# Adafruit_CH9328_UART_to_HID_Keyboard_Bre.net
KiCad netlist of a schematic drawn in EAGLE
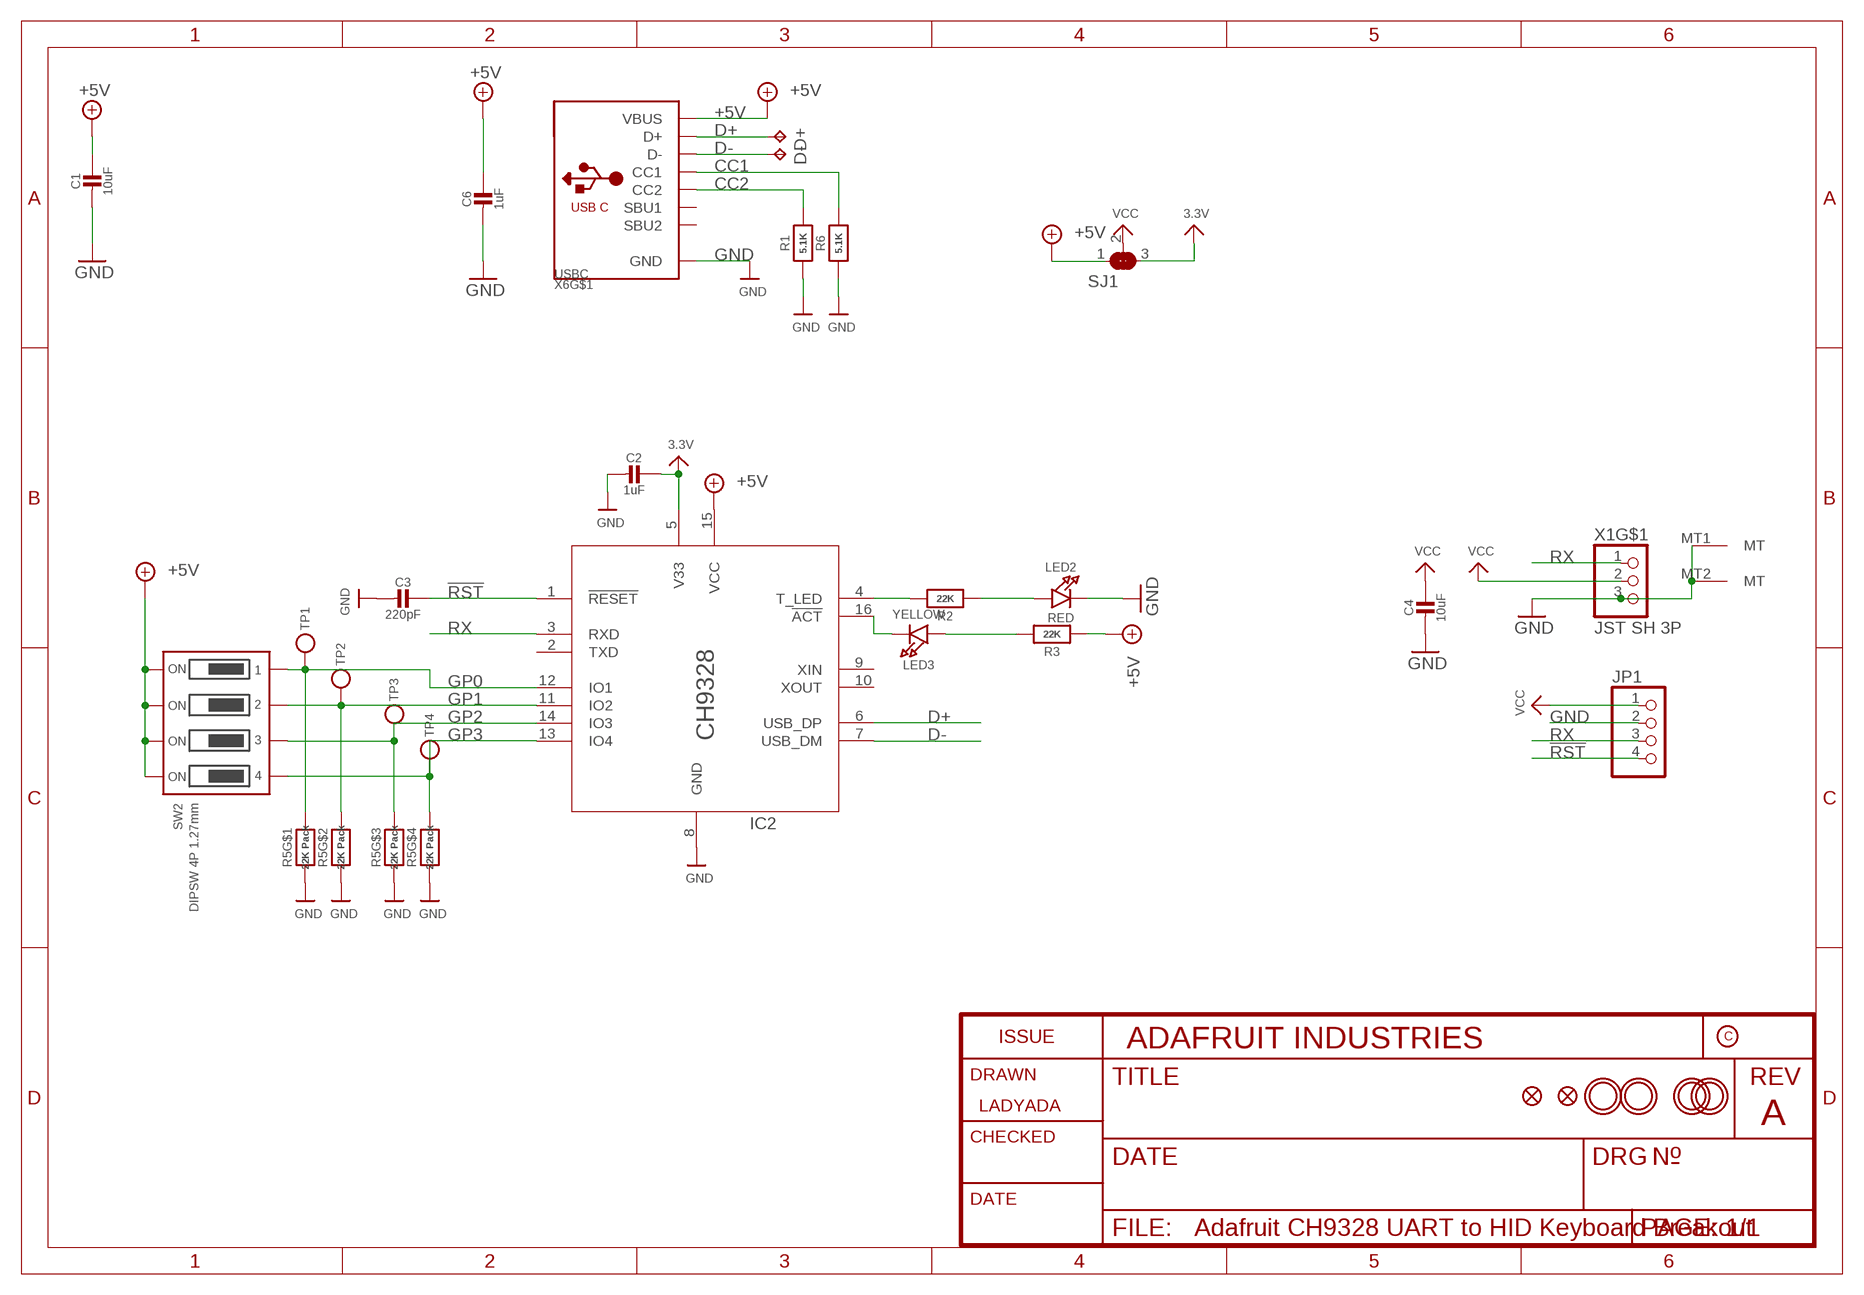
[diagram p0: schematic, sheet 1]

(export (version "E")
  (design (tool "Eeschema 10.0.6"))
  (components
    (comp (ref "C1")
      (value "10uF")
      (footprint "eagle-import:0805-NO")
      (libsource (lib "eagle-import") (part "CAP_CERAMIC0805-NOOUTLINE"))
    )
    (comp (ref "C2")
      (value "1uF")
      (footprint "eagle-import:0603-NO")
      (libsource (lib "eagle-import") (part "CAP_CERAMIC0603_NO"))
    )
    (comp (ref "C3")
      (value "220pF")
      (footprint "eagle-import:0603-NO")
      (libsource (lib "eagle-import") (part "CAP_CERAMIC0603_NO"))
    )
    (comp (ref "C4")
      (value "10uF")
      (footprint "eagle-import:0805-NO")
      (libsource (lib "eagle-import") (part "CAP_CERAMIC0805-NOOUTLINE"))
    )
    (comp (ref "C6")
      (value "1uF")
      (footprint "eagle-import:0603-NO")
      (libsource (lib "eagle-import") (part "CAP_CERAMIC0603_NO"))
    )
    (comp (ref "D+")
      (value "TPTP17R")
      (footprint "eagle-import:TP17R")
      (libsource (lib "eagle-import") (part "TPTP17R"))
    )
    (comp (ref "D-")
      (value "TPTP17R")
      (footprint "eagle-import:TP17R")
      (libsource (lib "eagle-import") (part "TPTP17R"))
    )
    (comp (ref "FID1")
      (value "FIDUCIAL_0.5MM")
      (footprint "eagle-import:FIDUCIAL_0.5MM")
      (libsource (lib "eagle-import") (part "FIDUCIAL_0.5MM"))
    )
    (comp (ref "FID2")
      (value "FIDUCIAL_0.5MM")
      (footprint "eagle-import:FIDUCIAL_0.5MM")
      (libsource (lib "eagle-import") (part "FIDUCIAL_0.5MM"))
    )
    (comp (ref "IC2")
      (value "CH9328_SKINNY")
      (footprint "eagle-import:SO16_SKINNY")
      (libsource (lib "eagle-import") (part "CH9328_SKINNY"))
    )
    (comp (ref "JP1")
      (value "HEADER-1X4ROUND")
      (footprint "eagle-import:1X04_ROUND")
      (libsource (lib "eagle-import") (part "HEADER-1X4ROUND"))
    )
    (comp (ref "LED2")
      (value "RED")
      (footprint "eagle-import:CHIPLED_0603_NOOUTLINE")
      (libsource (lib "eagle-import") (part "LED0603_NOOUTLINE"))
    )
    (comp (ref "LED3")
      (value "YELLOW")
      (footprint "eagle-import:CHIPLED_0603_NOOUTLINE")
      (libsource (lib "eagle-import") (part "LED0603_NOOUTLINE"))
    )
    (comp (ref "R1")
      (value "5.1K")
      (footprint "eagle-import:0603-NO")
      (libsource (lib "eagle-import") (part "RESISTOR_0603_NOOUT"))
    )
    (comp (ref "R2")
      (value "22K")
      (footprint "eagle-import:0603-NO")
      (libsource (lib "eagle-import") (part "RESISTOR_0603_NOOUT"))
    )
    (comp (ref "R3")
      (value "22K")
      (footprint "eagle-import:0603-NO")
      (libsource (lib "eagle-import") (part "RESISTOR_0603_NOOUT"))
    )
    (comp (ref "R5")
      (value "22K Pack")
      (footprint "eagle-import:RESPACK_4X0603")
      (libsource (lib "eagle-import") (part "RESISTOR_4PACK"))
    )
    (comp (ref "R6")
      (value "5.1K")
      (footprint "eagle-import:0603-NO")
      (libsource (lib "eagle-import") (part "RESISTOR_0603_NOOUT"))
    )
    (comp (ref "SJ1")
      (value "SOLDERJUMPER_2WAY")
      (footprint "eagle-import:SOLDERJUMPER_2WAY_OPEN_NOPASTE")
      (libsource (lib "eagle-import") (part "SOLDERJUMPER_2WAY"))
    )
    (comp (ref "SW2")
      (value "DIPSW 4P 1.27mm")
      (footprint "eagle-import:DIPSWITCH_4PIN_1.27")
      (libsource (lib "eagle-import") (part "DIPSWITCH_4PIN_1.27"))
    )
    (comp (ref "TP1")
      (value "TESTPOINTROUND1.5MMNO")
      (footprint "eagle-import:TESTPOINT_ROUND_1.5MM_NO")
      (libsource (lib "eagle-import") (part "TESTPOINTROUND1.5MMNO"))
    )
    (comp (ref "TP2")
      (value "TESTPOINTROUND1.5MMNO")
      (footprint "eagle-import:TESTPOINT_ROUND_1.5MM_NO")
      (libsource (lib "eagle-import") (part "TESTPOINTROUND1.5MMNO"))
    )
    (comp (ref "TP3")
      (value "TESTPOINTROUND1.5MMNO")
      (footprint "eagle-import:TESTPOINT_ROUND_1.5MM_NO")
      (libsource (lib "eagle-import") (part "TESTPOINTROUND1.5MMNO"))
    )
    (comp (ref "TP4")
      (value "TESTPOINTROUND1.5MMNO")
      (footprint "eagle-import:TESTPOINT_ROUND_1.5MM_NO")
      (libsource (lib "eagle-import") (part "TESTPOINTROUND1.5MMNO"))
    )
    (comp (ref "U$2")
      (value "MOUNTINGHOLE2.5")
      (footprint "eagle-import:MOUNTINGHOLE_2.5_PLATED")
      (fields (field (name "REV") "B"))
      (libsource (lib "eagle-import") (part "MOUNTINGHOLE2.5"))
    )
    (comp (ref "U$3")
      (value "MOUNTINGHOLE2.5")
      (footprint "eagle-import:MOUNTINGHOLE_2.5_PLATED")
      (fields (field (name "REV") "B"))
      (libsource (lib "eagle-import") (part "MOUNTINGHOLE2.5"))
    )
    (comp (ref "U$6")
      (value "MOUNTINGHOLE2.5")
      (footprint "eagle-import:MOUNTINGHOLE_2.5_PLATED")
      (fields (field (name "BOM") "EXCLUDE") (field (name "REV") "B"))
      (libsource (lib "eagle-import") (part "MOUNTINGHOLE2.5"))
    )
    (comp (ref "U$7")
      (value "MOUNTINGHOLE2.5")
      (footprint "eagle-import:MOUNTINGHOLE_2.5_PLATED")
      (libsource (lib "eagle-import") (part "MOUNTINGHOLE2.5"))
    )
    (comp (ref "X1")
      (value "JST SH 3P")
      (footprint "eagle-import:JST_SH3")
      (libsource (lib "eagle-import") (part "CON_JST_SH_3PINHORZ"))
    )
    (comp (ref "X6")
      (value "USBC")
      (footprint "eagle-import:USB_C_CUSB31-CFM2AX-01-X")
      (libsource (lib "eagle-import") (part "USB_C"))
    )
  )
  (nets
    (net (code "1") (name "+5V") (class "Default")
      (node (ref "C1") (pin "1") (pinfunction "1_1") (pintype "passive"))
      (node (ref "C6") (pin "1") (pinfunction "1_1") (pintype "passive"))
      (node (ref "IC2") (pin "15") (pinfunction "VCC_15") (pintype "power_in"))
      (node (ref "R3") (pin "1") (pinfunction "1_1") (pintype "passive"))
      (node (ref "SJ1") (pin "1") (pinfunction "1_1") (pintype "passive"))
      (node (ref "SW2") (pin "1ON") (pinfunction "1ON_1ON") (pintype "bidirectional"))
      (node (ref "SW2") (pin "2ON") (pinfunction "2ON_2ON") (pintype "bidirectional"))
      (node (ref "SW2") (pin "3ON") (pinfunction "3ON_3ON") (pintype "bidirectional"))
      (node (ref "SW2") (pin "4ON") (pinfunction "4ON_4ON") (pintype "bidirectional"))
      (node (ref "X6") (pin "A4B9") (pinfunction "VBUS_A4B9") (pintype "power_in"))
      (node (ref "X6") (pin "B4A9") (pinfunction "VBUS_B4A9") (pintype "power_in"))
    )
    (net (code "2") (name "/CC1") (class "Default")
      (node (ref "R6") (pin "2") (pinfunction "2_2") (pintype "passive"))
      (node (ref "X6") (pin "A5") (pinfunction "CC1_A5") (pintype "bidirectional"))
    )
    (net (code "3") (name "/CC2") (class "Default")
      (node (ref "R1") (pin "2") (pinfunction "2_2") (pintype "passive"))
      (node (ref "X6") (pin "B5") (pinfunction "CC2_B5") (pintype "bidirectional"))
    )
    (net (code "4") (name "/D+") (class "Default")
      (node (ref "D+") (pin "TP") (pinfunction "TP_TP") (pintype "input"))
      (node (ref "IC2") (pin "6") (pinfunction "USB_DP_6") (pintype "bidirectional"))
      (node (ref "X6") (pin "A6") (pinfunction "D+_A6") (pintype "bidirectional"))
      (node (ref "X6") (pin "B6") (pinfunction "D+_B6") (pintype "bidirectional"))
    )
    (net (code "5") (name "/D-") (class "Default")
      (node (ref "D-") (pin "TP") (pinfunction "TP_TP") (pintype "input"))
      (node (ref "IC2") (pin "7") (pinfunction "USB_DM_7") (pintype "bidirectional"))
      (node (ref "X6") (pin "A7") (pinfunction "D-_A7") (pintype "bidirectional"))
      (node (ref "X6") (pin "B7") (pinfunction "D-_B7") (pintype "bidirectional"))
    )
    (net (code "6") (name "/GP0") (class "Default")
      (node (ref "IC2") (pin "12") (pinfunction "IO1_12") (pintype "bidirectional"))
      (node (ref "R5") (pin "8") (pinfunction "2_8") (pintype "passive"))
      (node (ref "SW2") (pin "1OFF") (pinfunction "1OFF_1OFF") (pintype "bidirectional"))
      (node (ref "TP1") (pin "P$1") (pinfunction "P$1_P$1") (pintype "bidirectional"))
    )
    (net (code "7") (name "/GP1") (class "Default")
      (node (ref "IC2") (pin "11") (pinfunction "IO2_11") (pintype "bidirectional"))
      (node (ref "R5") (pin "7") (pinfunction "2_7") (pintype "passive"))
      (node (ref "SW2") (pin "2OFF") (pinfunction "2OFF_2OFF") (pintype "bidirectional"))
      (node (ref "TP2") (pin "P$1") (pinfunction "P$1_P$1") (pintype "bidirectional"))
    )
    (net (code "8") (name "/GP2") (class "Default")
      (node (ref "IC2") (pin "14") (pinfunction "IO3_14") (pintype "bidirectional"))
      (node (ref "R5") (pin "6") (pinfunction "2_6") (pintype "passive"))
      (node (ref "SW2") (pin "3OFF") (pinfunction "3OFF_3OFF") (pintype "bidirectional"))
      (node (ref "TP3") (pin "P$1") (pinfunction "P$1_P$1") (pintype "bidirectional"))
    )
    (net (code "9") (name "/GP3") (class "Default")
      (node (ref "IC2") (pin "13") (pinfunction "IO4_13") (pintype "bidirectional"))
      (node (ref "R5") (pin "5") (pinfunction "2_5") (pintype "passive"))
      (node (ref "SW2") (pin "4OFF") (pinfunction "4OFF_4OFF") (pintype "bidirectional"))
      (node (ref "TP4") (pin "P$1") (pinfunction "P$1_P$1") (pintype "bidirectional"))
    )
    (net (code "10") (name "/RX") (class "Default")
      (node (ref "IC2") (pin "3") (pinfunction "RXD_3") (pintype "bidirectional"))
      (node (ref "JP1") (pin "3") (pinfunction "3_3") (pintype "passive"))
      (node (ref "X1") (pin "1") (pinfunction "1_1") (pintype "passive"))
    )
    (net (code "11") (name "/~{RST}") (class "Default")
      (node (ref "C3") (pin "1") (pinfunction "1_1") (pintype "passive"))
      (node (ref "IC2") (pin "1") (pinfunction "~{RESET}_1") (pintype "bidirectional"))
      (node (ref "JP1") (pin "4") (pinfunction "4_4") (pintype "passive"))
    )
    (net (code "12") (name "3.3V") (class "Default")
      (node (ref "C2") (pin "1") (pinfunction "1_1") (pintype "passive"))
      (node (ref "IC2") (pin "5") (pinfunction "V33_5") (pintype "power_in"))
      (node (ref "SJ1") (pin "3") (pinfunction "3_3") (pintype "passive"))
    )
    (net (code "13") (name "GND") (class "Default")
      (node (ref "C1") (pin "2") (pinfunction "2_2") (pintype "passive"))
      (node (ref "C2") (pin "2") (pinfunction "2_2") (pintype "passive"))
      (node (ref "C3") (pin "2") (pinfunction "2_2") (pintype "passive"))
      (node (ref "C4") (pin "2") (pinfunction "2_2") (pintype "passive"))
      (node (ref "C6") (pin "2") (pinfunction "2_2") (pintype "passive"))
      (node (ref "IC2") (pin "8") (pinfunction "GND_8") (pintype "power_in"))
      (node (ref "JP1") (pin "2") (pinfunction "2_2") (pintype "passive"))
      (node (ref "LED2") (pin "C") (pinfunction "C_C") (pintype "passive"))
      (node (ref "R1") (pin "1") (pinfunction "1_1") (pintype "passive"))
      (node (ref "R5") (pin "1") (pinfunction "1_1") (pintype "passive"))
      (node (ref "R5") (pin "2") (pinfunction "1_2") (pintype "passive"))
      (node (ref "R5") (pin "3") (pinfunction "1_3") (pintype "passive"))
      (node (ref "R5") (pin "4") (pinfunction "1_4") (pintype "passive"))
      (node (ref "R6") (pin "1") (pinfunction "1_1") (pintype "passive"))
      (node (ref "X1") (pin "3") (pinfunction "3_3") (pintype "passive"))
      (node (ref "X1") (pin "MT1") (pinfunction "MT_MT1") (pintype "bidirectional"))
      (node (ref "X1") (pin "MT2") (pinfunction "MT_MT2") (pintype "bidirectional"))
      (node (ref "X6") (pin "A1B12") (pinfunction "GND_A1B12") (pintype "power_in"))
      (node (ref "X6") (pin "B1A12") (pinfunction "GND_B1A12") (pintype "power_in"))
    )
    (net (code "14") (name "Net-(IC2-T_LED)") (class "Default")
      (node (ref "IC2") (pin "4") (pinfunction "T_LED_4") (pintype "bidirectional"))
      (node (ref "R2") (pin "2") (pinfunction "2_2") (pintype "passive"))
    )
    (net (code "15") (name "Net-(IC2-~{ACT})") (class "Default")
      (node (ref "IC2") (pin "16") (pinfunction "~{ACT}_16") (pintype "bidirectional"))
      (node (ref "LED3") (pin "C") (pinfunction "C_C") (pintype "passive"))
    )
    (net (code "16") (name "Net-(LED2-PadA)") (class "Default")
      (node (ref "LED2") (pin "A") (pinfunction "A_A") (pintype "passive"))
      (node (ref "R2") (pin "1") (pinfunction "1_1") (pintype "passive"))
    )
    (net (code "17") (name "Net-(LED3-PadA)") (class "Default")
      (node (ref "LED3") (pin "A") (pinfunction "A_A") (pintype "passive"))
      (node (ref "R3") (pin "2") (pinfunction "2_2") (pintype "passive"))
    )
    (net (code "18") (name "VCC") (class "Default")
      (node (ref "C4") (pin "1") (pinfunction "1_1") (pintype "passive"))
      (node (ref "JP1") (pin "1") (pinfunction "1_1") (pintype "passive"))
      (node (ref "SJ1") (pin "2") (pinfunction "2_2") (pintype "passive"))
      (node (ref "X1") (pin "2") (pinfunction "2_2") (pintype "passive"))
    )
    (net (code "19") (name "unconnected-(IC2-TXD-Pad2)") (class "Default")
      (node (ref "IC2") (pin "2") (pinfunction "TXD_2") (pintype "bidirectional"))
    )
    (net (code "20") (name "unconnected-(IC2-XIN-Pad9)") (class "Default")
      (node (ref "IC2") (pin "9") (pinfunction "XIN_9") (pintype "bidirectional"))
    )
    (net (code "21") (name "unconnected-(IC2-XOUT-Pad10)") (class "Default")
      (node (ref "IC2") (pin "10") (pinfunction "XOUT_10") (pintype "bidirectional"))
    )
    (net (code "22") (name "unconnected-(X6A-SBU1-PadA8)") (class "Default")
      (node (ref "X6") (pin "A8") (pinfunction "SBU1_A8") (pintype "bidirectional"))
    )
    (net (code "23") (name "unconnected-(X6A-SBU2-PadB8)") (class "Default")
      (node (ref "X6") (pin "B8") (pinfunction "SBU2_B8") (pintype "bidirectional"))
    )
  )
)
